# Teensy_Tester.net
KiCad netlist of a schematic drawn in EasyEDA
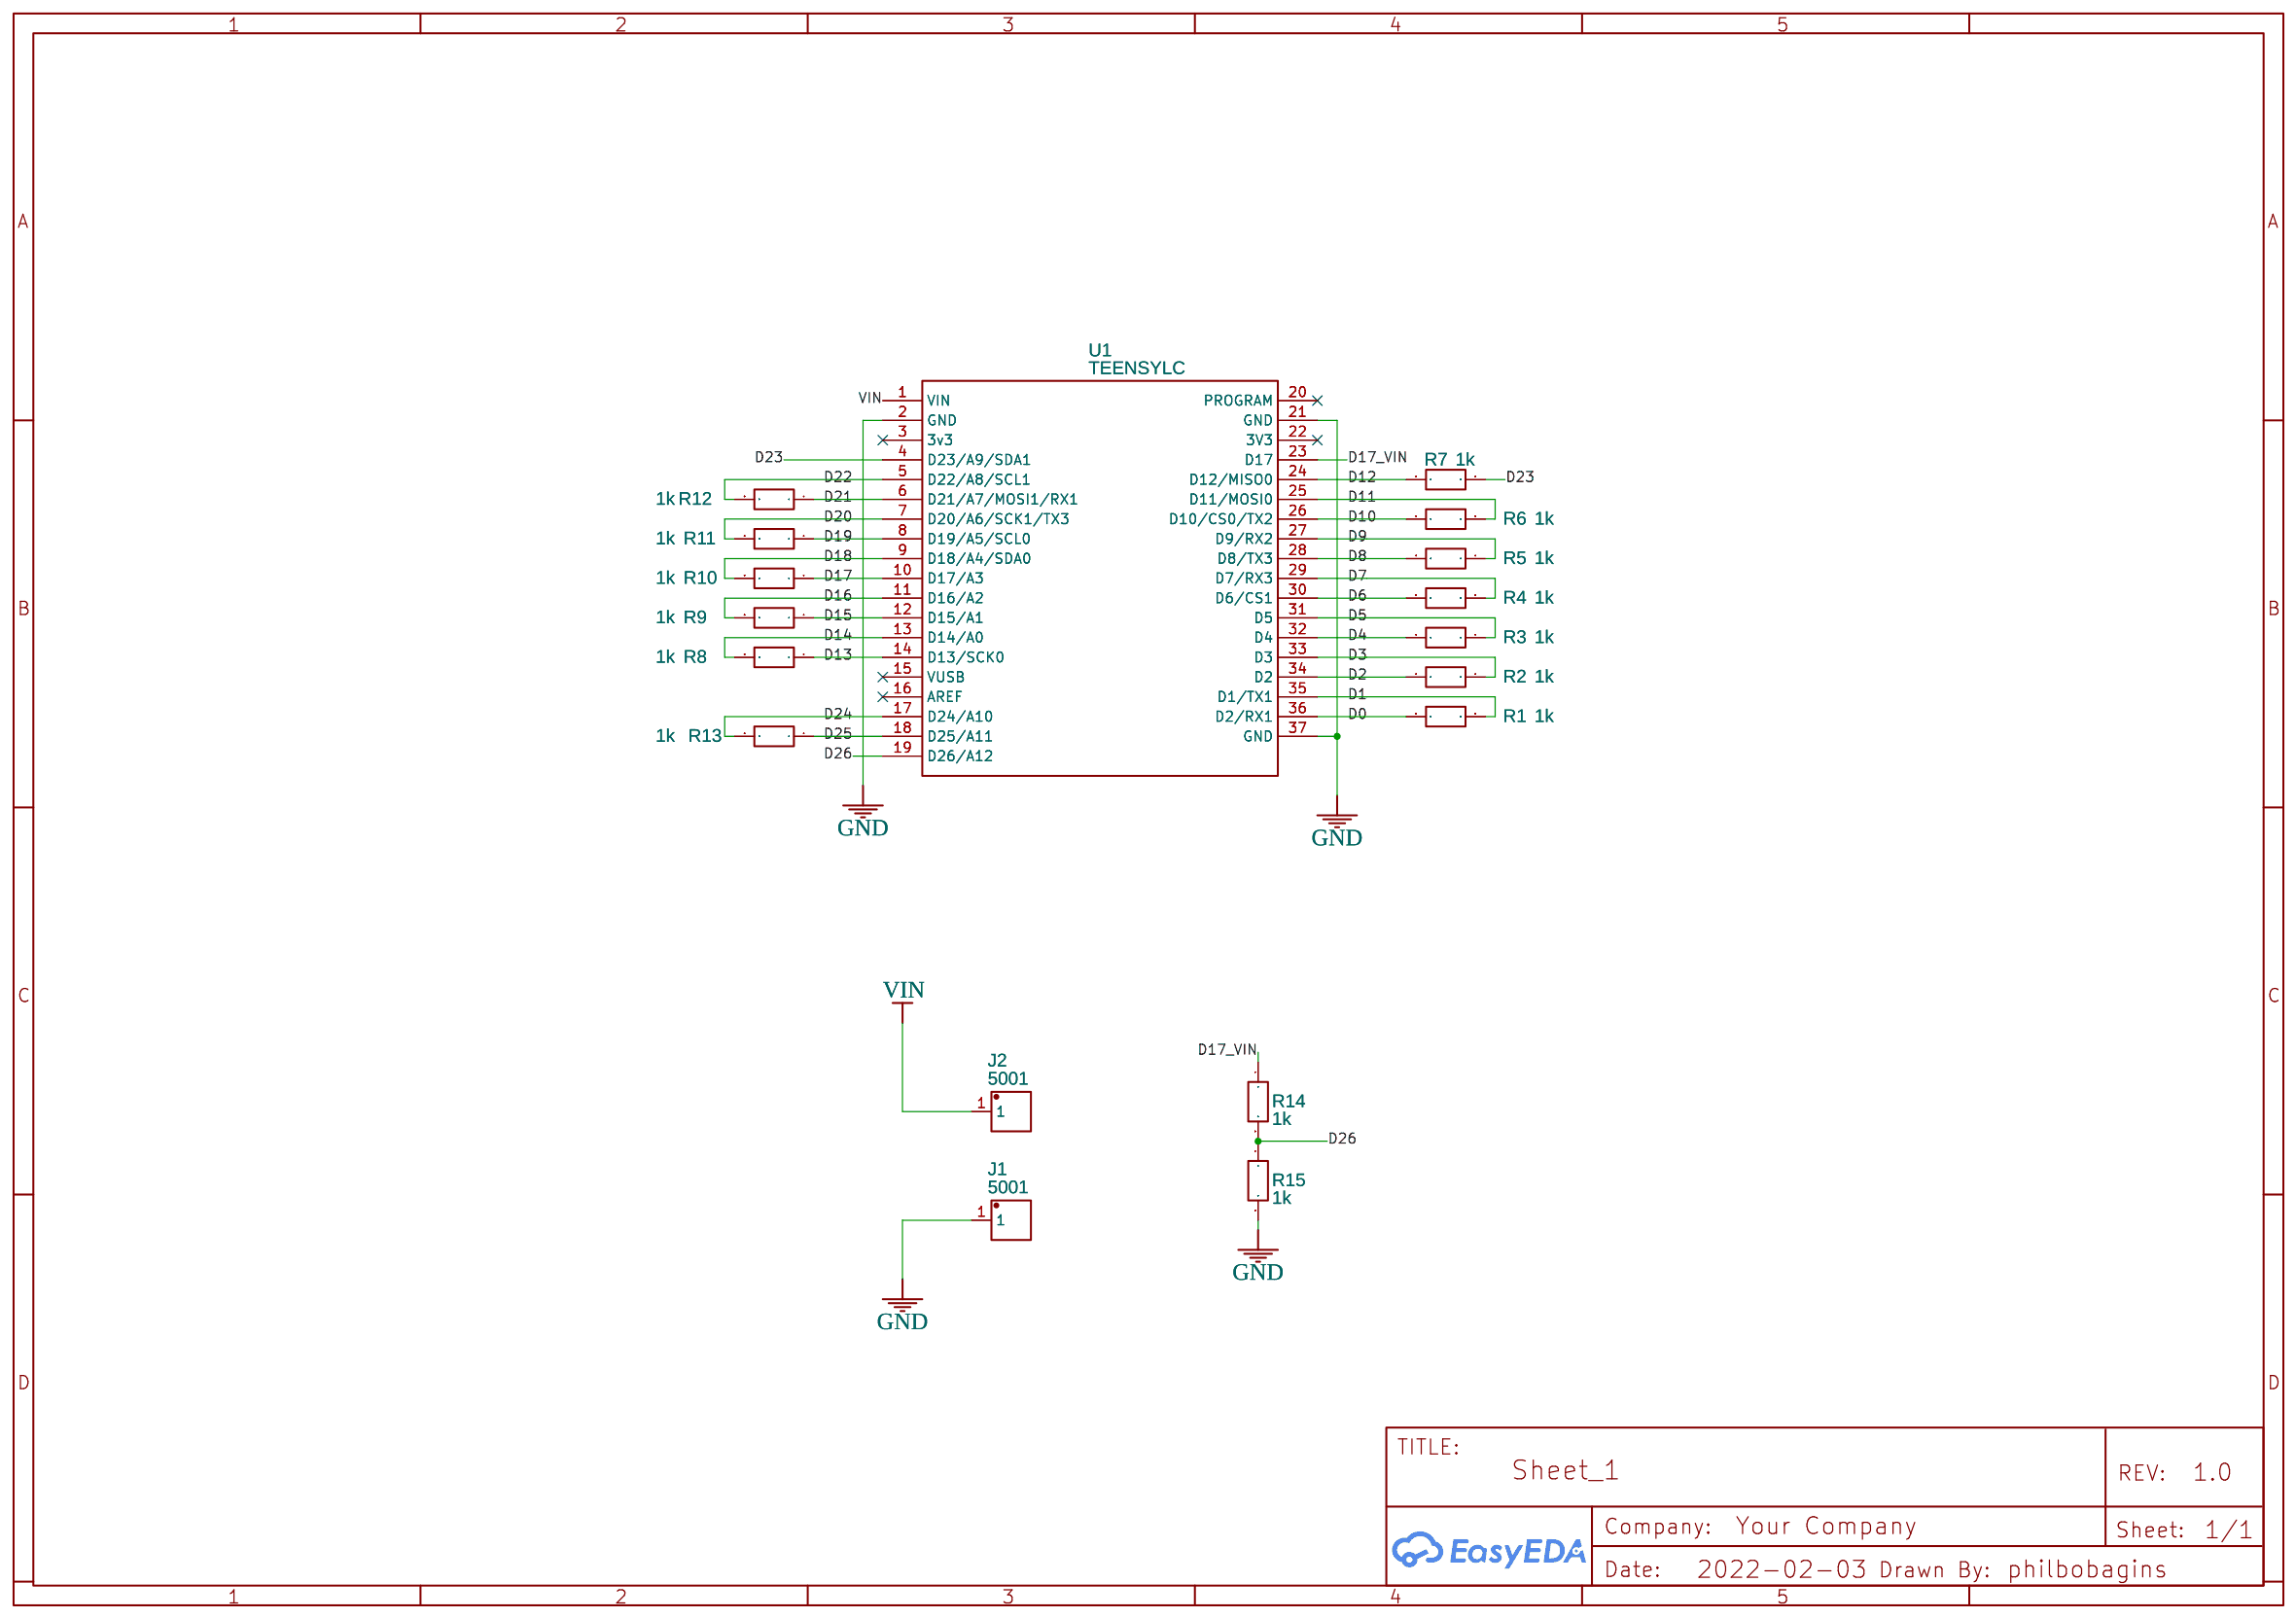
[diagram p0: schematic sheet]

(export (version "E")
  (design (tool "Eeschema 10.0.6"))
  (components
    (comp (ref "J1")
      (value "5001")
      (fields (field (name "BOM_Supplier Part") "C238122"))
      (libsource (lib "") (part "5001"))
    )
    (comp (ref "J2")
      (value "5001")
      (fields (field (name "BOM_Supplier Part") "C238122"))
      (libsource (lib "") (part "5001"))
    )
    (comp (ref "R1") (value "1k") (libsource (lib "") (part "R_0603_EU")))
    (comp (ref "R2") (value "1k") (libsource (lib "") (part "R_0603_EU")))
    (comp (ref "R3") (value "1k") (libsource (lib "") (part "R_0603_EU")))
    (comp (ref "R4") (value "1k") (libsource (lib "") (part "R_0603_EU")))
    (comp (ref "R5") (value "1k") (libsource (lib "") (part "R_0603_EU")))
    (comp (ref "R6") (value "1k") (libsource (lib "") (part "R_0603_EU")))
    (comp (ref "R7") (value "1k") (libsource (lib "") (part "R_0603_EU")))
    (comp (ref "R8") (value "1k") (libsource (lib "") (part "R_0603_EU")))
    (comp (ref "R9") (value "1k") (libsource (lib "") (part "R_0603_EU")))
    (comp (ref "R10") (value "1k") (libsource (lib "") (part "R_0603_EU")))
    (comp (ref "R11") (value "1k") (libsource (lib "") (part "R_0603_EU")))
    (comp (ref "R12") (value "1k") (libsource (lib "") (part "R_0603_EU")))
    (comp (ref "R13") (value "1k") (libsource (lib "") (part "R_0603_EU")))
    (comp (ref "R14") (value "1k") (libsource (lib "") (part "R_0603_EU_1")))
    (comp (ref "R15") (value "1k") (libsource (lib "") (part "R_0603_EU_1")))
    (comp (ref "U1") (value "TEENSYLC") (libsource (lib "") (part "TEENSYLC")))
  )
  (nets
    (net (code "1") (name "/D0") (class "Default")
      (node (ref "R1") (pin "2") (pinfunction "2_2") (pintype "unspecified"))
      (node (ref "U1") (pin "36") (pinfunction "D2/RX1_36") (pintype "unspecified"))
    )
    (net (code "2") (name "/D1") (class "Default")
      (node (ref "R1") (pin "1") (pinfunction "1_1") (pintype "unspecified"))
      (node (ref "U1") (pin "35") (pinfunction "D1/TX1_35") (pintype "unspecified"))
    )
    (net (code "3") (name "/D2") (class "Default")
      (node (ref "R2") (pin "2") (pinfunction "2_2") (pintype "unspecified"))
      (node (ref "U1") (pin "34") (pinfunction "D2_34") (pintype "unspecified"))
    )
    (net (code "4") (name "/D3") (class "Default")
      (node (ref "R2") (pin "1") (pinfunction "1_1") (pintype "unspecified"))
      (node (ref "U1") (pin "33") (pinfunction "D3_33") (pintype "unspecified"))
    )
    (net (code "5") (name "/D4") (class "Default")
      (node (ref "R3") (pin "2") (pinfunction "2_2") (pintype "unspecified"))
      (node (ref "U1") (pin "32") (pinfunction "D4_32") (pintype "unspecified"))
    )
    (net (code "6") (name "/D5") (class "Default")
      (node (ref "R3") (pin "1") (pinfunction "1_1") (pintype "unspecified"))
      (node (ref "U1") (pin "31") (pinfunction "D5_31") (pintype "unspecified"))
    )
    (net (code "7") (name "/D6") (class "Default")
      (node (ref "R4") (pin "2") (pinfunction "2_2") (pintype "unspecified"))
      (node (ref "U1") (pin "30") (pinfunction "D6/CS1_30") (pintype "unspecified"))
    )
    (net (code "8") (name "/D7") (class "Default")
      (node (ref "R4") (pin "1") (pinfunction "1_1") (pintype "unspecified"))
      (node (ref "U1") (pin "29") (pinfunction "D7/RX3_29") (pintype "unspecified"))
    )
    (net (code "9") (name "/D8") (class "Default")
      (node (ref "R5") (pin "2") (pinfunction "2_2") (pintype "unspecified"))
      (node (ref "U1") (pin "28") (pinfunction "D8/TX3_28") (pintype "unspecified"))
    )
    (net (code "10") (name "/D9") (class "Default")
      (node (ref "R5") (pin "1") (pinfunction "1_1") (pintype "unspecified"))
      (node (ref "U1") (pin "27") (pinfunction "D9/RX2_27") (pintype "unspecified"))
    )
    (net (code "11") (name "/D10") (class "Default")
      (node (ref "R6") (pin "2") (pinfunction "2_2") (pintype "unspecified"))
      (node (ref "U1") (pin "26") (pinfunction "D10/CS0/TX2_26") (pintype "unspecified"))
    )
    (net (code "12") (name "/D11") (class "Default")
      (node (ref "R6") (pin "1") (pinfunction "1_1") (pintype "unspecified"))
      (node (ref "U1") (pin "25") (pinfunction "D11/MOSI0_25") (pintype "unspecified"))
    )
    (net (code "13") (name "/D12") (class "Default")
      (node (ref "R7") (pin "2") (pinfunction "2_2") (pintype "unspecified"))
      (node (ref "U1") (pin "24") (pinfunction "D12/MISO0_24") (pintype "unspecified"))
    )
    (net (code "14") (name "/D13") (class "Default")
      (node (ref "R8") (pin "1") (pinfunction "1_1") (pintype "unspecified"))
      (node (ref "U1") (pin "14") (pinfunction "D13/SCK0_14") (pintype "unspecified"))
    )
    (net (code "15") (name "/D14") (class "Default")
      (node (ref "R8") (pin "2") (pinfunction "2_2") (pintype "unspecified"))
      (node (ref "U1") (pin "13") (pinfunction "D14/A0_13") (pintype "unspecified"))
    )
    (net (code "16") (name "/D15") (class "Default")
      (node (ref "R9") (pin "1") (pinfunction "1_1") (pintype "unspecified"))
      (node (ref "U1") (pin "12") (pinfunction "D15/A1_12") (pintype "unspecified"))
    )
    (net (code "17") (name "/D16") (class "Default")
      (node (ref "R9") (pin "2") (pinfunction "2_2") (pintype "unspecified"))
      (node (ref "U1") (pin "11") (pinfunction "D16/A2_11") (pintype "unspecified"))
    )
    (net (code "18") (name "/D17") (class "Default")
      (node (ref "R10") (pin "1") (pinfunction "1_1") (pintype "unspecified"))
      (node (ref "U1") (pin "10") (pinfunction "D17/A3_10") (pintype "unspecified"))
    )
    (net (code "19") (name "/D17_VIN") (class "Default")
      (node (ref "R14") (pin "1") (pinfunction "1_1") (pintype "unspecified"))
      (node (ref "U1") (pin "23") (pinfunction "D17_23") (pintype "unspecified"))
    )
    (net (code "20") (name "/D18") (class "Default")
      (node (ref "R10") (pin "2") (pinfunction "2_2") (pintype "unspecified"))
      (node (ref "U1") (pin "9") (pinfunction "D18/A4/SDA0_9") (pintype "unspecified"))
    )
    (net (code "21") (name "/D19") (class "Default")
      (node (ref "R11") (pin "1") (pinfunction "1_1") (pintype "unspecified"))
      (node (ref "U1") (pin "8") (pinfunction "D19/A5/SCL0_8") (pintype "unspecified"))
    )
    (net (code "22") (name "/D20") (class "Default")
      (node (ref "R11") (pin "2") (pinfunction "2_2") (pintype "unspecified"))
      (node (ref "U1") (pin "7") (pinfunction "D20/A6/SCK1/TX3_7") (pintype "unspecified"))
    )
    (net (code "23") (name "/D21") (class "Default")
      (node (ref "R12") (pin "1") (pinfunction "1_1") (pintype "unspecified"))
      (node (ref "U1") (pin "6") (pinfunction "D21/A7/MOSI1/RX1_6") (pintype "unspecified"))
    )
    (net (code "24") (name "/D22") (class "Default")
      (node (ref "R12") (pin "2") (pinfunction "2_2") (pintype "unspecified"))
      (node (ref "U1") (pin "5") (pinfunction "D22/A8/SCL1_5") (pintype "unspecified"))
    )
    (net (code "25") (name "/D23") (class "Default")
      (node (ref "R7") (pin "1") (pinfunction "1_1") (pintype "unspecified"))
      (node (ref "U1") (pin "4") (pinfunction "D23/A9/SDA1_4") (pintype "unspecified"))
    )
    (net (code "26") (name "/D24") (class "Default")
      (node (ref "R13") (pin "2") (pinfunction "2_2") (pintype "unspecified"))
      (node (ref "U1") (pin "17") (pinfunction "D24/A10_17") (pintype "unspecified"))
    )
    (net (code "27") (name "/D25") (class "Default")
      (node (ref "R13") (pin "1") (pinfunction "1_1") (pintype "unspecified"))
      (node (ref "U1") (pin "18") (pinfunction "D25/A11_18") (pintype "unspecified"))
    )
    (net (code "28") (name "/D26") (class "Default")
      (node (ref "R14") (pin "2") (pinfunction "2_2") (pintype "unspecified"))
      (node (ref "R15") (pin "1") (pinfunction "1_1") (pintype "unspecified"))
      (node (ref "U1") (pin "19") (pinfunction "D26/A12_19") (pintype "unspecified"))
    )
    (net (code "29") (name "GND") (class "Default")
      (node (ref "J1") (pin "1") (pinfunction "1_1") (pintype "unspecified"))
      (node (ref "R15") (pin "2") (pinfunction "2_2") (pintype "unspecified"))
      (node (ref "U1") (pin "2") (pinfunction "GND_2") (pintype "unspecified"))
      (node (ref "U1") (pin "21") (pinfunction "GND_21") (pintype "unspecified"))
      (node (ref "U1") (pin "37") (pinfunction "GND_37") (pintype "unspecified"))
    )
    (net (code "30") (name "VIN") (class "Default")
      (node (ref "J2") (pin "1") (pinfunction "1_1") (pintype "unspecified"))
      (node (ref "U1") (pin "1") (pinfunction "VIN_1") (pintype "unspecified"))
    )
    (net (code "31") (name "unconnected-(U1-3V3-Pad22)") (class "Default")
      (node (ref "U1") (pin "22") (pinfunction "3V3_22") (pintype "unspecified+no_connect"))
    )
    (net (code "32") (name "unconnected-(U1-3v3-Pad3)") (class "Default")
      (node (ref "U1") (pin "3") (pinfunction "3v3_3") (pintype "unspecified+no_connect"))
    )
    (net (code "33") (name "unconnected-(U1-AREF-Pad16)") (class "Default")
      (node (ref "U1") (pin "16") (pinfunction "AREF_16") (pintype "unspecified+no_connect"))
    )
    (net (code "34") (name "unconnected-(U1-PROGRAM-Pad20)") (class "Default")
      (node (ref "U1") (pin "20") (pinfunction "PROGRAM_20") (pintype "unspecified+no_connect"))
    )
    (net (code "35") (name "unconnected-(U1-VUSB-Pad15)") (class "Default")
      (node (ref "U1") (pin "15") (pinfunction "VUSB_15") (pintype "unspecified+no_connect"))
    )
  )
)
